# MCU.net
KiCad netlist of a schematic drawn in Altium Designer
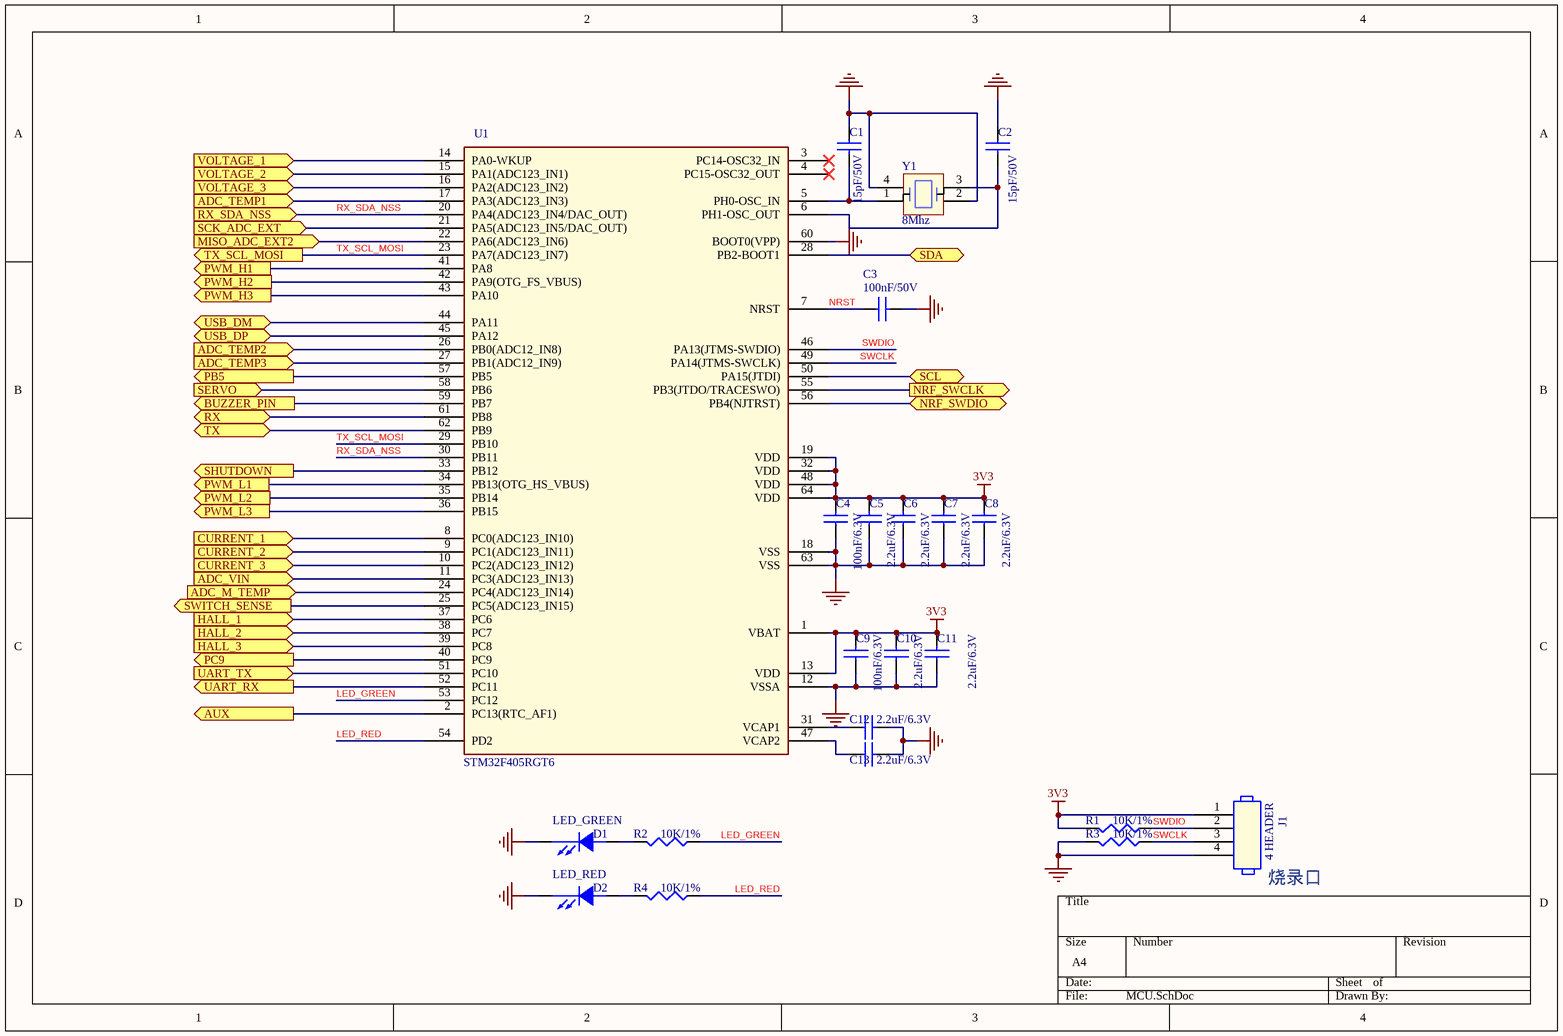
[diagram p0: MCU.SchDoc]

(export (version "E")
  (design (tool "Eeschema 10.0.6"))
  (components
    (comp (ref "C1") (value "15pF/50V") (footprint "C0402") (libsource (lib "*") (part "CAP NP")))
    (comp (ref "C2") (value "15pF/50V") (footprint "C0402") (libsource (lib "*") (part "CAP NP")))
    (comp (ref "C3") (value "100nF/50V") (footprint "C0402") (libsource (lib "*") (part "CAP NP")))
    (comp (ref "C4") (value "100nF/6.3V") (footprint "C0402") (libsource (lib "*") (part "CAP NP")))
    (comp (ref "C5") (value "2.2uF/6.3V") (footprint "C0402") (libsource (lib "*") (part "CAP NP")))
    (comp (ref "C6") (value "2.2uF/6.3V") (footprint "C0402") (libsource (lib "*") (part "CAP NP")))
    (comp (ref "C7") (value "2.2uF/6.3V") (footprint "C0402") (libsource (lib "*") (part "CAP NP")))
    (comp (ref "C8") (value "2.2uF/6.3V") (footprint "C0402") (libsource (lib "*") (part "CAP NP")))
    (comp (ref "C9") (value "100nF/6.3V") (footprint "C0402") (libsource (lib "*") (part "CAP NP")))
    (comp (ref "C10") (value "2.2uF/6.3V") (footprint "C0402") (libsource (lib "*") (part "CAP NP")))
    (comp (ref "C11") (value "2.2uF/6.3V") (footprint "C0402") (libsource (lib "*") (part "CAP NP")))
    (comp (ref "C12") (value "2.2uF/6.3V") (footprint "C0402") (libsource (lib "*") (part "CAP NP")))
    (comp (ref "C13") (value "2.2uF/6.3V") (footprint "C0402") (libsource (lib "*") (part "CAP NP")))
    (comp (ref "D1") (value "LED_GREEN") (footprint "LED0603") (libsource (lib "*") (part "LED")))
    (comp (ref "D2") (value "LED_RED") (footprint "LED0603") (libsource (lib "*") (part "LED")))
    (comp (ref "J1") (value "4 HEADER") (footprint "ISP-4P-2_54") (libsource (lib "*") (part "4 HEADER")))
    (comp (ref "R1") (value "10K/1%") (footprint "R0402") (libsource (lib "*") (part "RESISTOR")))
    (comp (ref "R2") (value "10K/1%") (footprint "R0402") (libsource (lib "*") (part "RESISTOR")))
    (comp (ref "R3") (value "10K/1%") (footprint "R0402") (libsource (lib "*") (part "RESISTOR")))
    (comp (ref "R4") (value "10K/1%") (footprint "R0402") (libsource (lib "*") (part "RESISTOR")))
    (comp (ref "U1")
      (value "STM32F405RGT6")
      (footprint "LQFP64_10X10_05P")
      (libsource (lib "VESC_DEVICE_Library") (part "STM32F405RGT6"))
    )
    (comp (ref "Y1")
      (value "8Mhz")
      (footprint "CRYSTAL-SMD_4P-L3.2-W2.5-BL")
      (description "Crystal or Oscillator")
      (fields (field (name "MANUFACTURER_PART_NUMBER") "Q22FA12800400"))
      (libsource (lib "VESC_DEVICE_Library") (part "8Mhz"))
    )
  )
  (nets
    (net (code "1") (name "/ADC_M_TEMP") (class "Default")
      (node (ref "U1") (pin "24") (pinfunction "PC4(ADC123_IN14)_24") (pintype "passive"))
    )
    (net (code "2") (name "/ADC_TEMP1") (class "Default")
      (node (ref "U1") (pin "17") (pinfunction "PA3(ADC123_IN3)_17") (pintype "passive"))
    )
    (net (code "3") (name "/ADC_TEMP2") (class "Default")
      (node (ref "U1") (pin "26") (pinfunction "PB0(ADC12_IN8)_26") (pintype "passive"))
    )
    (net (code "4") (name "/ADC_TEMP3") (class "Default")
      (node (ref "U1") (pin "27") (pinfunction "PB1(ADC12_IN9)_27") (pintype "passive"))
    )
    (net (code "5") (name "/ADC_VIN") (class "Default")
      (node (ref "U1") (pin "11") (pinfunction "PC3(ADC123_IN13)_11") (pintype "passive"))
    )
    (net (code "6") (name "/AUX") (class "Default")
      (node (ref "U1") (pin "2") (pinfunction "PC13(RTC_AF1)_2") (pintype "passive"))
    )
    (net (code "7") (name "/BUZZER_PIN") (class "Default")
      (node (ref "U1") (pin "59") (pinfunction "PB7_59") (pintype "passive"))
    )
    (net (code "8") (name "/CURRENT_1") (class "Default")
      (node (ref "U1") (pin "8") (pinfunction "PC0(ADC123_IN10)_8") (pintype "passive"))
    )
    (net (code "9") (name "/CURRENT_2") (class "Default")
      (node (ref "U1") (pin "9") (pinfunction "PC1(ADC123_IN11)_9") (pintype "passive"))
    )
    (net (code "10") (name "/CURRENT_3") (class "Default")
      (node (ref "U1") (pin "10") (pinfunction "PC2(ADC123_IN12)_10") (pintype "passive"))
    )
    (net (code "11") (name "/HALL_1") (class "Default")
      (node (ref "U1") (pin "37") (pinfunction "PC6_37") (pintype "passive"))
    )
    (net (code "12") (name "/HALL_2") (class "Default")
      (node (ref "U1") (pin "38") (pinfunction "PC7_38") (pintype "passive"))
    )
    (net (code "13") (name "/HALL_3") (class "Default")
      (node (ref "U1") (pin "39") (pinfunction "PC8_39") (pintype "passive"))
    )
    (net (code "14") (name "/LED_GREEN") (class "Default")
      (node (ref "R2") (pin "1") (pinfunction "1_1") (pintype "passive"))
      (node (ref "U1") (pin "53") (pinfunction "PC12_53") (pintype "passive"))
    )
    (net (code "15") (name "/LED_RED") (class "Default")
      (node (ref "R4") (pin "1") (pinfunction "1_1") (pintype "passive"))
      (node (ref "U1") (pin "54") (pinfunction "PD2_54") (pintype "passive"))
    )
    (net (code "16") (name "/MISO_ADC_EXT2") (class "Default")
      (node (ref "U1") (pin "22") (pinfunction "PA6(ADC123_IN6)_22") (pintype "passive"))
    )
    (net (code "17") (name "/NRF_SWCLK") (class "Default")
      (node (ref "U1") (pin "55") (pinfunction "PB3(JTDO/TRACESWO)_55") (pintype "passive"))
    )
    (net (code "18") (name "/NRF_SWDIO") (class "Default")
      (node (ref "U1") (pin "56") (pinfunction "PB4(NJTRST)_56") (pintype "passive"))
    )
    (net (code "19") (name "/NRST") (class "Default")
      (node (ref "C3") (pin "1") (pinfunction "1_1") (pintype "passive"))
      (node (ref "U1") (pin "7") (pinfunction "NRST_7") (pintype "passive"))
    )
    (net (code "20") (name "/PB5") (class "Default")
      (node (ref "U1") (pin "57") (pinfunction "PB5_57") (pintype "passive"))
    )
    (net (code "21") (name "/PC9") (class "Default")
      (node (ref "U1") (pin "40") (pinfunction "PC9_40") (pintype "passive"))
    )
    (net (code "22") (name "/PWM_H1") (class "Default")
      (node (ref "U1") (pin "41") (pinfunction "PA8_41") (pintype "passive"))
    )
    (net (code "23") (name "/PWM_H2") (class "Default")
      (node (ref "U1") (pin "42") (pinfunction "PA9(OTG_FS_VBUS)_42") (pintype "passive"))
    )
    (net (code "24") (name "/PWM_H3") (class "Default")
      (node (ref "U1") (pin "43") (pinfunction "PA10_43") (pintype "passive"))
    )
    (net (code "25") (name "/PWM_L1") (class "Default")
      (node (ref "U1") (pin "34") (pinfunction "PB13(OTG_HS_VBUS)_34") (pintype "passive"))
    )
    (net (code "26") (name "/PWM_L2") (class "Default")
      (node (ref "U1") (pin "35") (pinfunction "PB14_35") (pintype "passive"))
    )
    (net (code "27") (name "/PWM_L3") (class "Default")
      (node (ref "U1") (pin "36") (pinfunction "PB15_36") (pintype "passive"))
    )
    (net (code "28") (name "/RX") (class "Default")
      (node (ref "U1") (pin "61") (pinfunction "PB8_61") (pintype "passive"))
    )
    (net (code "29") (name "/RX_SDA_NSS") (class "Default")
      (node (ref "U1") (pin "20") (pinfunction "PA4(ADC123_IN4/DAC_OUT)_20") (pintype "passive"))
      (node (ref "U1") (pin "30") (pinfunction "PB11_30") (pintype "passive"))
    )
    (net (code "30") (name "/SCK_ADC_EXT") (class "Default")
      (node (ref "U1") (pin "21") (pinfunction "PA5(ADC123_IN5/DAC_OUT)_21") (pintype "passive"))
    )
    (net (code "31") (name "/SCL") (class "Default")
      (node (ref "U1") (pin "50") (pinfunction "PA15(JTDI)_50") (pintype "passive"))
    )
    (net (code "32") (name "/SDA") (class "Default")
      (node (ref "U1") (pin "28") (pinfunction "PB2-BOOT1_28") (pintype "passive"))
    )
    (net (code "33") (name "/SERVO") (class "Default")
      (node (ref "U1") (pin "58") (pinfunction "PB6_58") (pintype "passive"))
    )
    (net (code "34") (name "/SHUTDOWN") (class "Default")
      (node (ref "U1") (pin "33") (pinfunction "PB12_33") (pintype "passive"))
    )
    (net (code "35") (name "/SWCLK") (class "Default")
      (node (ref "J1") (pin "3") (pinfunction "3_3") (pintype "passive"))
      (node (ref "R3") (pin "1") (pinfunction "1_1") (pintype "passive"))
      (node (ref "U1") (pin "49") (pinfunction "PA14(JTMS-SWCLK)_49") (pintype "passive"))
    )
    (net (code "36") (name "/SWDIO") (class "Default")
      (node (ref "J1") (pin "2") (pinfunction "2_2") (pintype "passive"))
      (node (ref "R1") (pin "1") (pinfunction "1_1") (pintype "passive"))
      (node (ref "U1") (pin "46") (pinfunction "PA13(JTMS-SWDIO)_46") (pintype "passive"))
    )
    (net (code "37") (name "/SWITCH_SENSE") (class "Default")
      (node (ref "U1") (pin "25") (pinfunction "PC5(ADC123_IN15)_25") (pintype "passive"))
    )
    (net (code "38") (name "/TX") (class "Default")
      (node (ref "U1") (pin "62") (pinfunction "PB9_62") (pintype "passive"))
    )
    (net (code "39") (name "/TX_SCL_MOSI") (class "Default")
      (node (ref "U1") (pin "23") (pinfunction "PA7(ADC123_IN7)_23") (pintype "passive"))
      (node (ref "U1") (pin "29") (pinfunction "PB10_29") (pintype "passive"))
    )
    (net (code "40") (name "/UART_RX") (class "Default")
      (node (ref "U1") (pin "52") (pinfunction "PC11_52") (pintype "passive"))
    )
    (net (code "41") (name "/UART_TX") (class "Default")
      (node (ref "U1") (pin "51") (pinfunction "PC10_51") (pintype "passive"))
    )
    (net (code "42") (name "/USB_DM") (class "Default")
      (node (ref "U1") (pin "44") (pinfunction "PA11_44") (pintype "passive"))
    )
    (net (code "43") (name "/USB_DP") (class "Default")
      (node (ref "U1") (pin "45") (pinfunction "PA12_45") (pintype "passive"))
    )
    (net (code "44") (name "/VOLTAGE_1") (class "Default")
      (node (ref "U1") (pin "14") (pinfunction "PA0-WKUP_14") (pintype "passive"))
    )
    (net (code "45") (name "/VOLTAGE_2") (class "Default")
      (node (ref "U1") (pin "15") (pinfunction "PA1(ADC123_IN1)_15") (pintype "passive"))
    )
    (net (code "46") (name "/VOLTAGE_3") (class "Default")
      (node (ref "U1") (pin "16") (pinfunction "PA2(ADC123_IN2)_16") (pintype "passive"))
    )
    (net (code "47") (name "3V3") (class "Default")
      (node (ref "C10") (pin "2") (pinfunction "2_2") (pintype "passive"))
      (node (ref "C11") (pin "2") (pinfunction "2_2") (pintype "passive"))
      (node (ref "C4") (pin "2") (pinfunction "2_2") (pintype "passive"))
      (node (ref "C5") (pin "2") (pinfunction "2_2") (pintype "passive"))
      (node (ref "C6") (pin "2") (pinfunction "2_2") (pintype "passive"))
      (node (ref "C7") (pin "2") (pinfunction "2_2") (pintype "passive"))
      (node (ref "C8") (pin "2") (pinfunction "2_2") (pintype "passive"))
      (node (ref "C9") (pin "2") (pinfunction "2_2") (pintype "passive"))
      (node (ref "J1") (pin "1") (pinfunction "1_1") (pintype "passive"))
      (node (ref "R1") (pin "2") (pinfunction "2_2") (pintype "passive"))
      (node (ref "U1") (pin "1") (pinfunction "VBAT_1") (pintype "power_in"))
      (node (ref "U1") (pin "13") (pinfunction "VDD_13") (pintype "power_in"))
      (node (ref "U1") (pin "19") (pinfunction "VDD_19") (pintype "power_in"))
      (node (ref "U1") (pin "32") (pinfunction "VDD_32") (pintype "power_in"))
      (node (ref "U1") (pin "48") (pinfunction "VDD_48") (pintype "power_in"))
      (node (ref "U1") (pin "64") (pinfunction "VDD_64") (pintype "power_in"))
    )
    (net (code "48") (name "GND") (class "Default")
      (node (ref "C1") (pin "1") (pinfunction "1_1") (pintype "passive"))
      (node (ref "C10") (pin "1") (pinfunction "1_1") (pintype "passive"))
      (node (ref "C11") (pin "1") (pinfunction "1_1") (pintype "passive"))
      (node (ref "C12") (pin "2") (pinfunction "2_2") (pintype "passive"))
      (node (ref "C13") (pin "2") (pinfunction "2_2") (pintype "passive"))
      (node (ref "C2") (pin "1") (pinfunction "1_1") (pintype "passive"))
      (node (ref "C3") (pin "2") (pinfunction "2_2") (pintype "passive"))
      (node (ref "C4") (pin "1") (pinfunction "1_1") (pintype "passive"))
      (node (ref "C5") (pin "1") (pinfunction "1_1") (pintype "passive"))
      (node (ref "C6") (pin "1") (pinfunction "1_1") (pintype "passive"))
      (node (ref "C7") (pin "1") (pinfunction "1_1") (pintype "passive"))
      (node (ref "C8") (pin "1") (pinfunction "1_1") (pintype "passive"))
      (node (ref "C9") (pin "1") (pinfunction "1_1") (pintype "passive"))
      (node (ref "D1") (pin "1") (pinfunction "CATHODE_1") (pintype "passive"))
      (node (ref "D2") (pin "1") (pinfunction "CATHODE_1") (pintype "passive"))
      (node (ref "J1") (pin "4") (pinfunction "4_4") (pintype "passive"))
      (node (ref "R3") (pin "2") (pinfunction "2_2") (pintype "passive"))
      (node (ref "U1") (pin "12") (pinfunction "VSSA_12") (pintype "power_in"))
      (node (ref "U1") (pin "18") (pinfunction "VSS_18") (pintype "power_in"))
      (node (ref "U1") (pin "60") (pinfunction "BOOT0(VPP)_60") (pintype "passive"))
      (node (ref "U1") (pin "63") (pinfunction "VSS_63") (pintype "power_in"))
      (node (ref "Y1") (pin "2") (pinfunction "GND_1_2") (pintype "passive"))
      (node (ref "Y1") (pin "4") (pinfunction "GND_2_4") (pintype "passive"))
    )
    (net (code "49") (name "Net-(D1-ANODE)") (class "Default")
      (node (ref "D1") (pin "2") (pinfunction "ANODE_2") (pintype "passive"))
      (node (ref "R2") (pin "2") (pinfunction "2_2") (pintype "passive"))
    )
    (net (code "50") (name "Net-(D2-ANODE)") (class "Default")
      (node (ref "D2") (pin "2") (pinfunction "ANODE_2") (pintype "passive"))
      (node (ref "R4") (pin "2") (pinfunction "2_2") (pintype "passive"))
    )
    (net (code "51") (name "Net-(U1-PH0-OSC_IN)") (class "Default")
      (node (ref "C1") (pin "2") (pinfunction "2_2") (pintype "passive"))
      (node (ref "U1") (pin "5") (pinfunction "PH0-OSC_IN_5") (pintype "passive"))
      (node (ref "Y1") (pin "1") (pinfunction "CRYSTAL_1_1") (pintype "passive"))
    )
    (net (code "52") (name "Net-(U1-PH1-OSC_OUT)") (class "Default")
      (node (ref "C2") (pin "2") (pinfunction "2_2") (pintype "passive"))
      (node (ref "U1") (pin "6") (pinfunction "PH1-OSC_OUT_6") (pintype "passive"))
      (node (ref "Y1") (pin "3") (pinfunction "CRYSTAL_2_3") (pintype "passive"))
    )
    (net (code "53") (name "Net-(U1-VCAP1)") (class "Default")
      (node (ref "C12") (pin "1") (pinfunction "1_1") (pintype "passive"))
      (node (ref "U1") (pin "31") (pinfunction "VCAP1_31") (pintype "passive"))
    )
    (net (code "54") (name "Net-(U1-VCAP2)") (class "Default")
      (node (ref "C13") (pin "1") (pinfunction "1_1") (pintype "passive"))
      (node (ref "U1") (pin "47") (pinfunction "VCAP2_47") (pintype "passive"))
    )
    (net (code "55") (name "unconnected-(U1-PC14-OSC32_IN-Pad3)") (class "Default")
      (node (ref "U1") (pin "3") (pinfunction "PC14-OSC32_IN_3") (pintype "passive+no_connect"))
    )
    (net (code "56") (name "unconnected-(U1-PC15-OSC32_OUT-Pad4)") (class "Default")
      (node (ref "U1") (pin "4") (pinfunction "PC15-OSC32_OUT_4") (pintype "passive+no_connect"))
    )
  )
)
